# lab2sch.net
KiCad netlist of a schematic drawn in EAGLE
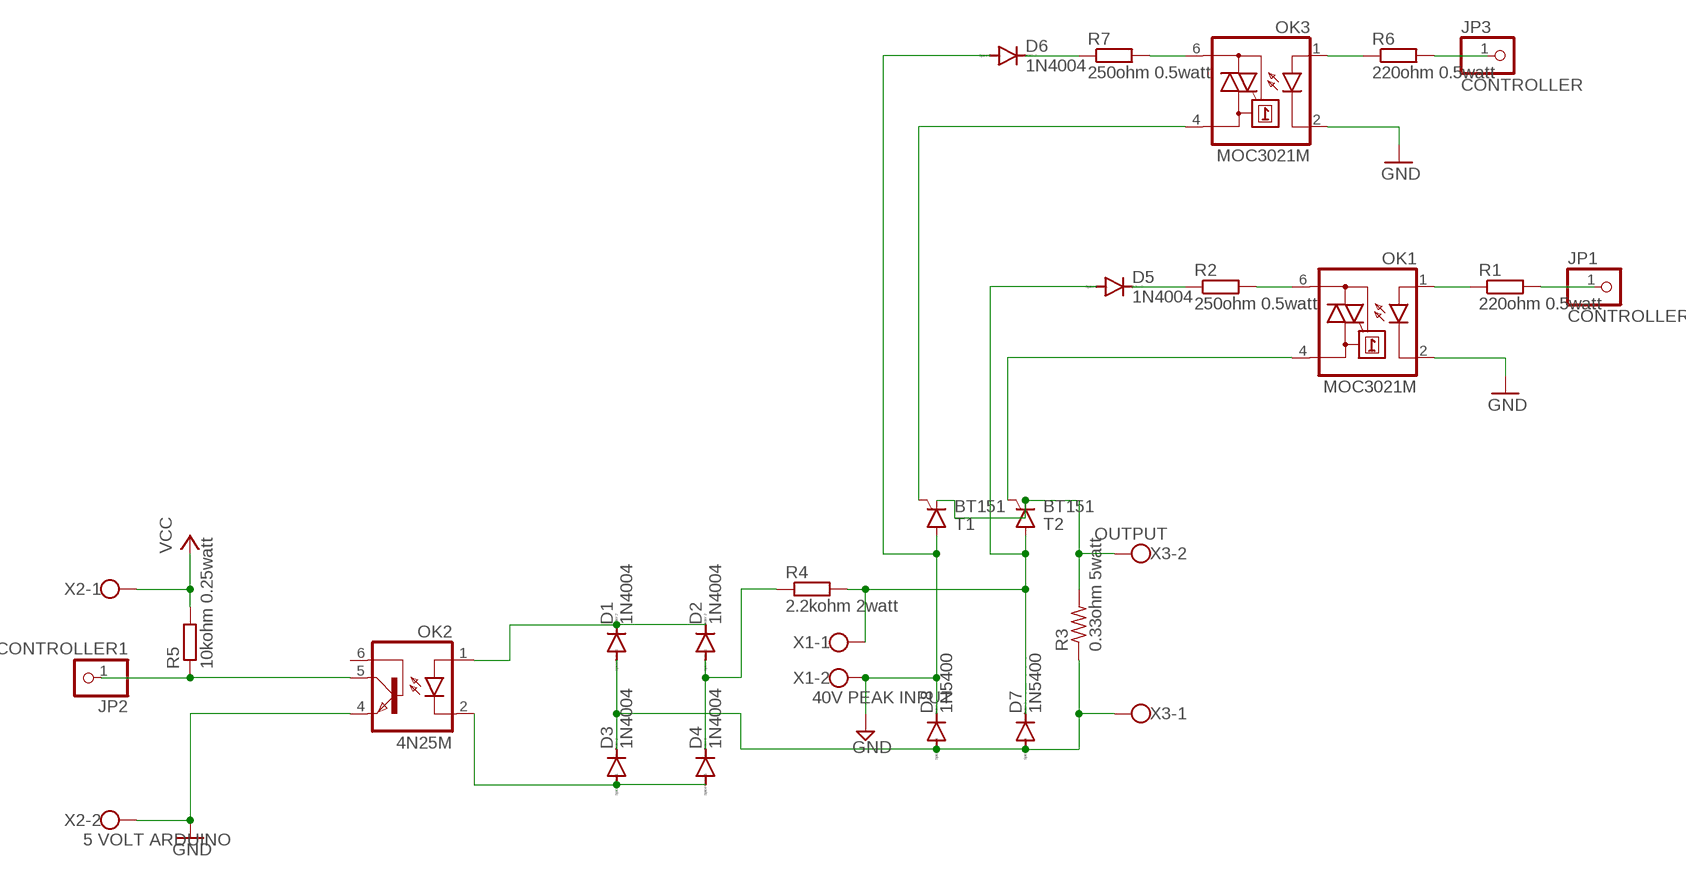
[diagram p0: schematic, sheet 1]

(export (version "E")
  (design (tool "Eeschema 10.0.6"))
  (components
    (comp (ref "D1")
      (value "1N4004")
      (footprint "eagle-import:DO41-10")
      (libsource (lib "eagle-import") (part "1N4004"))
    )
    (comp (ref "D2")
      (value "1N4004")
      (footprint "eagle-import:DO41-10")
      (libsource (lib "eagle-import") (part "1N4004"))
    )
    (comp (ref "D3")
      (value "1N4004")
      (footprint "eagle-import:DO41-10")
      (libsource (lib "eagle-import") (part "1N4004"))
    )
    (comp (ref "D4")
      (value "1N4004")
      (footprint "eagle-import:DO41-10")
      (libsource (lib "eagle-import") (part "1N4004"))
    )
    (comp (ref "D5")
      (value "1N4004")
      (footprint "eagle-import:DO41-10")
      (libsource (lib "eagle-import") (part "1N4004"))
    )
    (comp (ref "D6")
      (value "1N4004")
      (footprint "eagle-import:DO41-10")
      (libsource (lib "eagle-import") (part "1N4004"))
    )
    (comp (ref "D7")
      (value "1N5400")
      (footprint "eagle-import:DO201-15")
      (libsource (lib "eagle-import") (part "1N5400"))
    )
    (comp (ref "D8")
      (value "1N5400")
      (footprint "eagle-import:DO201-15")
      (libsource (lib "eagle-import") (part "1N5400"))
    )
    (comp (ref "JP1")
      (value "CONTROLLER")
      (footprint "eagle-import:1X01")
      (libsource (lib "eagle-import") (part "PINHD-1X1"))
    )
    (comp (ref "JP2")
      (value "CONTROLLER1")
      (footprint "eagle-import:1X01")
      (libsource (lib "eagle-import") (part "PINHD-1X1"))
    )
    (comp (ref "JP3")
      (value "CONTROLLER")
      (footprint "eagle-import:1X01")
      (libsource (lib "eagle-import") (part "PINHD-1X1"))
    )
    (comp (ref "OK1")
      (value "MOC3021M")
      (footprint "eagle-import:DIL06")
      (fields (field (name "MF") "FAIRCHILD SEMICONDUCTOR") (field (name "MPN") "MOC3021-M"))
      (libsource (lib "eagle-import") (part "MOC30M21"))
    )
    (comp (ref "OK2")
      (value "4N25M")
      (footprint "eagle-import:DIL06")
      (fields (field (name "MPN") "4N25-M"))
      (libsource (lib "eagle-import") (part "4N?M25"))
    )
    (comp (ref "OK3")
      (value "MOC3021M")
      (footprint "eagle-import:DIL06")
      (fields (field (name "MF") "FAIRCHILD SEMICONDUCTOR") (field (name "MPN") "MOC3021-M"))
      (libsource (lib "eagle-import") (part "MOC30M21"))
    )
    (comp (ref "R1")
      (value "220ohm 0.5watt")
      (footprint "eagle-import:0204_7")
      (libsource (lib "eagle-import") (part "R-EU_0204/7"))
    )
    (comp (ref "R2")
      (value "250ohm 0.5watt")
      (footprint "eagle-import:0207_10")
      (libsource (lib "eagle-import") (part "R-EU_0207/10"))
    )
    (comp (ref "R3")
      (value "0.33ohm 5watt")
      (footprint "eagle-import:0617_22")
      (libsource (lib "eagle-import") (part "R-US_0617/22"))
    )
    (comp (ref "R4")
      (value "2.2kohm 2watt")
      (footprint "eagle-import:0204_7")
      (libsource (lib "eagle-import") (part "R-EU_0204/7"))
    )
    (comp (ref "R5")
      (value "10kohm 0.25watt")
      (footprint "eagle-import:0204_7")
      (libsource (lib "eagle-import") (part "R-EU_0204/7"))
    )
    (comp (ref "R6")
      (value "220ohm 0.5watt")
      (footprint "eagle-import:0204_7")
      (libsource (lib "eagle-import") (part "R-EU_0204/7"))
    )
    (comp (ref "R7")
      (value "250ohm 0.5watt")
      (footprint "eagle-import:0207_10")
      (libsource (lib "eagle-import") (part "R-EU_0207/10"))
    )
    (comp (ref "T1")
      (value "BT151")
      (footprint "eagle-import:TO220CL")
      (libsource (lib "eagle-import") (part "BT151"))
    )
    (comp (ref "T2")
      (value "BT151")
      (footprint "eagle-import:TO220CL")
      (libsource (lib "eagle-import") (part "BT151"))
    )
    (comp (ref "X1")
      (value "40V PEAK INPUT")
      (footprint "eagle-import:W237-102")
      (fields (field (name "MPN") "237-102"))
      (libsource (lib "eagle-import") (part "W237-102"))
    )
    (comp (ref "X2")
      (value "5 VOLT ARDUINO")
      (footprint "eagle-import:W237-102")
      (fields (field (name "MPN") "237-102"))
      (libsource (lib "eagle-import") (part "W237-102"))
    )
    (comp (ref "X3")
      (value "OUTPUT")
      (footprint "eagle-import:W237-102")
      (fields (field (name "MPN") "237-102"))
      (libsource (lib "eagle-import") (part "W237-102"))
    )
  )
  (nets
    (net (code "1") (name "GND") (class "Default")
      (node (ref "D6") (pin "A") (pinfunction "A_A") (pintype "passive"))
      (node (ref "D8") (pin "C") (pinfunction "C_C") (pintype "passive"))
      (node (ref "OK1") (pin "2") (pinfunction "C_2") (pintype "passive"))
      (node (ref "OK2") (pin "4") (pinfunction "EMI_4") (pintype "passive"))
      (node (ref "OK3") (pin "2") (pinfunction "C_2") (pintype "passive"))
      (node (ref "T1") (pin "A") (pinfunction "A_A") (pintype "passive"))
      (node (ref "X1") (pin "2") (pinfunction "KL_2") (pintype "passive"))
      (node (ref "X2") (pin "2") (pinfunction "KL_2") (pintype "passive"))
    )
    (net (code "2") (name "Net-(D2-PadA)") (class "Default")
      (node (ref "D2") (pin "A") (pinfunction "A_A") (pintype "passive"))
      (node (ref "D4") (pin "C") (pinfunction "C_C") (pintype "passive"))
      (node (ref "R4") (pin "1") (pinfunction "1_1") (pintype "passive"))
    )
    (net (code "3") (name "Net-(D5-PadC)") (class "Default")
      (node (ref "D5") (pin "C") (pinfunction "C_C") (pintype "passive"))
      (node (ref "R2") (pin "1") (pinfunction "1_1") (pintype "passive"))
    )
    (net (code "4") (name "Net-(D6-PadC)") (class "Default")
      (node (ref "D6") (pin "C") (pinfunction "C_C") (pintype "passive"))
      (node (ref "R7") (pin "1") (pinfunction "1_1") (pintype "passive"))
    )
    (net (code "5") (name "Net-(JP1-Pad1)") (class "Default")
      (node (ref "JP1") (pin "1") (pinfunction "1_1") (pintype "passive"))
      (node (ref "R1") (pin "2") (pinfunction "2_2") (pintype "passive"))
    )
    (net (code "6") (name "Net-(JP3-Pad1)") (class "Default")
      (node (ref "JP3") (pin "1") (pinfunction "1_1") (pintype "passive"))
      (node (ref "R6") (pin "2") (pinfunction "2_2") (pintype "passive"))
    )
    (net (code "7") (name "Net-(OK1-A)") (class "Default")
      (node (ref "OK1") (pin "1") (pinfunction "A_1") (pintype "passive"))
      (node (ref "R1") (pin "1") (pinfunction "1_1") (pintype "passive"))
    )
    (net (code "8") (name "Net-(OK1-A1)") (class "Default")
      (node (ref "OK1") (pin "4") (pinfunction "A1_4") (pintype "passive"))
      (node (ref "T2") (pin "G") (pinfunction "G_G") (pintype "passive"))
    )
    (net (code "9") (name "Net-(OK1-A2)") (class "Default")
      (node (ref "OK1") (pin "6") (pinfunction "A2_6") (pintype "passive"))
      (node (ref "R2") (pin "2") (pinfunction "2_2") (pintype "passive"))
    )
    (net (code "10") (name "Net-(OK2-A)") (class "Default")
      (node (ref "D1") (pin "C") (pinfunction "C_C") (pintype "passive"))
      (node (ref "D2") (pin "C") (pinfunction "C_C") (pintype "passive"))
      (node (ref "OK2") (pin "1") (pinfunction "A_1") (pintype "passive"))
    )
    (net (code "11") (name "Net-(OK2-C)") (class "Default")
      (node (ref "D3") (pin "A") (pinfunction "A_A") (pintype "passive"))
      (node (ref "D4") (pin "A") (pinfunction "A_A") (pintype "passive"))
      (node (ref "OK2") (pin "2") (pinfunction "C_2") (pintype "passive"))
    )
    (net (code "12") (name "Net-(OK2-COL)") (class "Default")
      (node (ref "JP2") (pin "1") (pinfunction "1_1") (pintype "passive"))
      (node (ref "OK2") (pin "5") (pinfunction "COL_5") (pintype "passive"))
      (node (ref "R5") (pin "1") (pinfunction "1_1") (pintype "passive"))
    )
    (net (code "13") (name "Net-(OK3-A)") (class "Default")
      (node (ref "OK3") (pin "1") (pinfunction "A_1") (pintype "passive"))
      (node (ref "R6") (pin "1") (pinfunction "1_1") (pintype "passive"))
    )
    (net (code "14") (name "Net-(OK3-A1)") (class "Default")
      (node (ref "OK3") (pin "4") (pinfunction "A1_4") (pintype "passive"))
      (node (ref "T1") (pin "G") (pinfunction "G_G") (pintype "passive"))
    )
    (net (code "15") (name "Net-(OK3-A2)") (class "Default")
      (node (ref "OK3") (pin "6") (pinfunction "A2_6") (pintype "passive"))
      (node (ref "R7") (pin "2") (pinfunction "2_2") (pintype "passive"))
    )
    (net (code "16") (name "Net-(X1A-KL)") (class "Default")
      (node (ref "D5") (pin "A") (pinfunction "A_A") (pintype "passive"))
      (node (ref "D7") (pin "C") (pinfunction "C_C") (pintype "passive"))
      (node (ref "R4") (pin "2") (pinfunction "2_2") (pintype "passive"))
      (node (ref "T2") (pin "A") (pinfunction "A_A") (pintype "passive"))
      (node (ref "X1") (pin "1") (pinfunction "KL_1") (pintype "passive"))
    )
    (net (code "17") (name "Net-(X3A-KL)") (class "Default")
      (node (ref "D1") (pin "A") (pinfunction "A_A") (pintype "passive"))
      (node (ref "D3") (pin "C") (pinfunction "C_C") (pintype "passive"))
      (node (ref "D7") (pin "A") (pinfunction "A_A") (pintype "passive"))
      (node (ref "D8") (pin "A") (pinfunction "A_A") (pintype "passive"))
      (node (ref "R3") (pin "1") (pinfunction "1_1") (pintype "passive"))
      (node (ref "X3") (pin "1") (pinfunction "KL_1") (pintype "passive"))
    )
    (net (code "18") (name "Net-(X3B-KL)") (class "Default")
      (node (ref "R3") (pin "2") (pinfunction "2_2") (pintype "passive"))
      (node (ref "T1") (pin "C") (pinfunction "C_C") (pintype "passive"))
      (node (ref "T2") (pin "C") (pinfunction "C_C") (pintype "passive"))
      (node (ref "X3") (pin "2") (pinfunction "KL_2") (pintype "passive"))
    )
    (net (code "19") (name "VCC") (class "Default")
      (node (ref "R5") (pin "2") (pinfunction "2_2") (pintype "passive"))
      (node (ref "X2") (pin "1") (pinfunction "KL_1") (pintype "passive"))
    )
    (net (code "20") (name "unconnected-(OK2-BAS-Pad6)") (class "Default")
      (node (ref "OK2") (pin "6") (pinfunction "BAS_6") (pintype "passive"))
    )
  )
)
